# design.net
KiCad netlist of a schematic drawn in Altium Designer
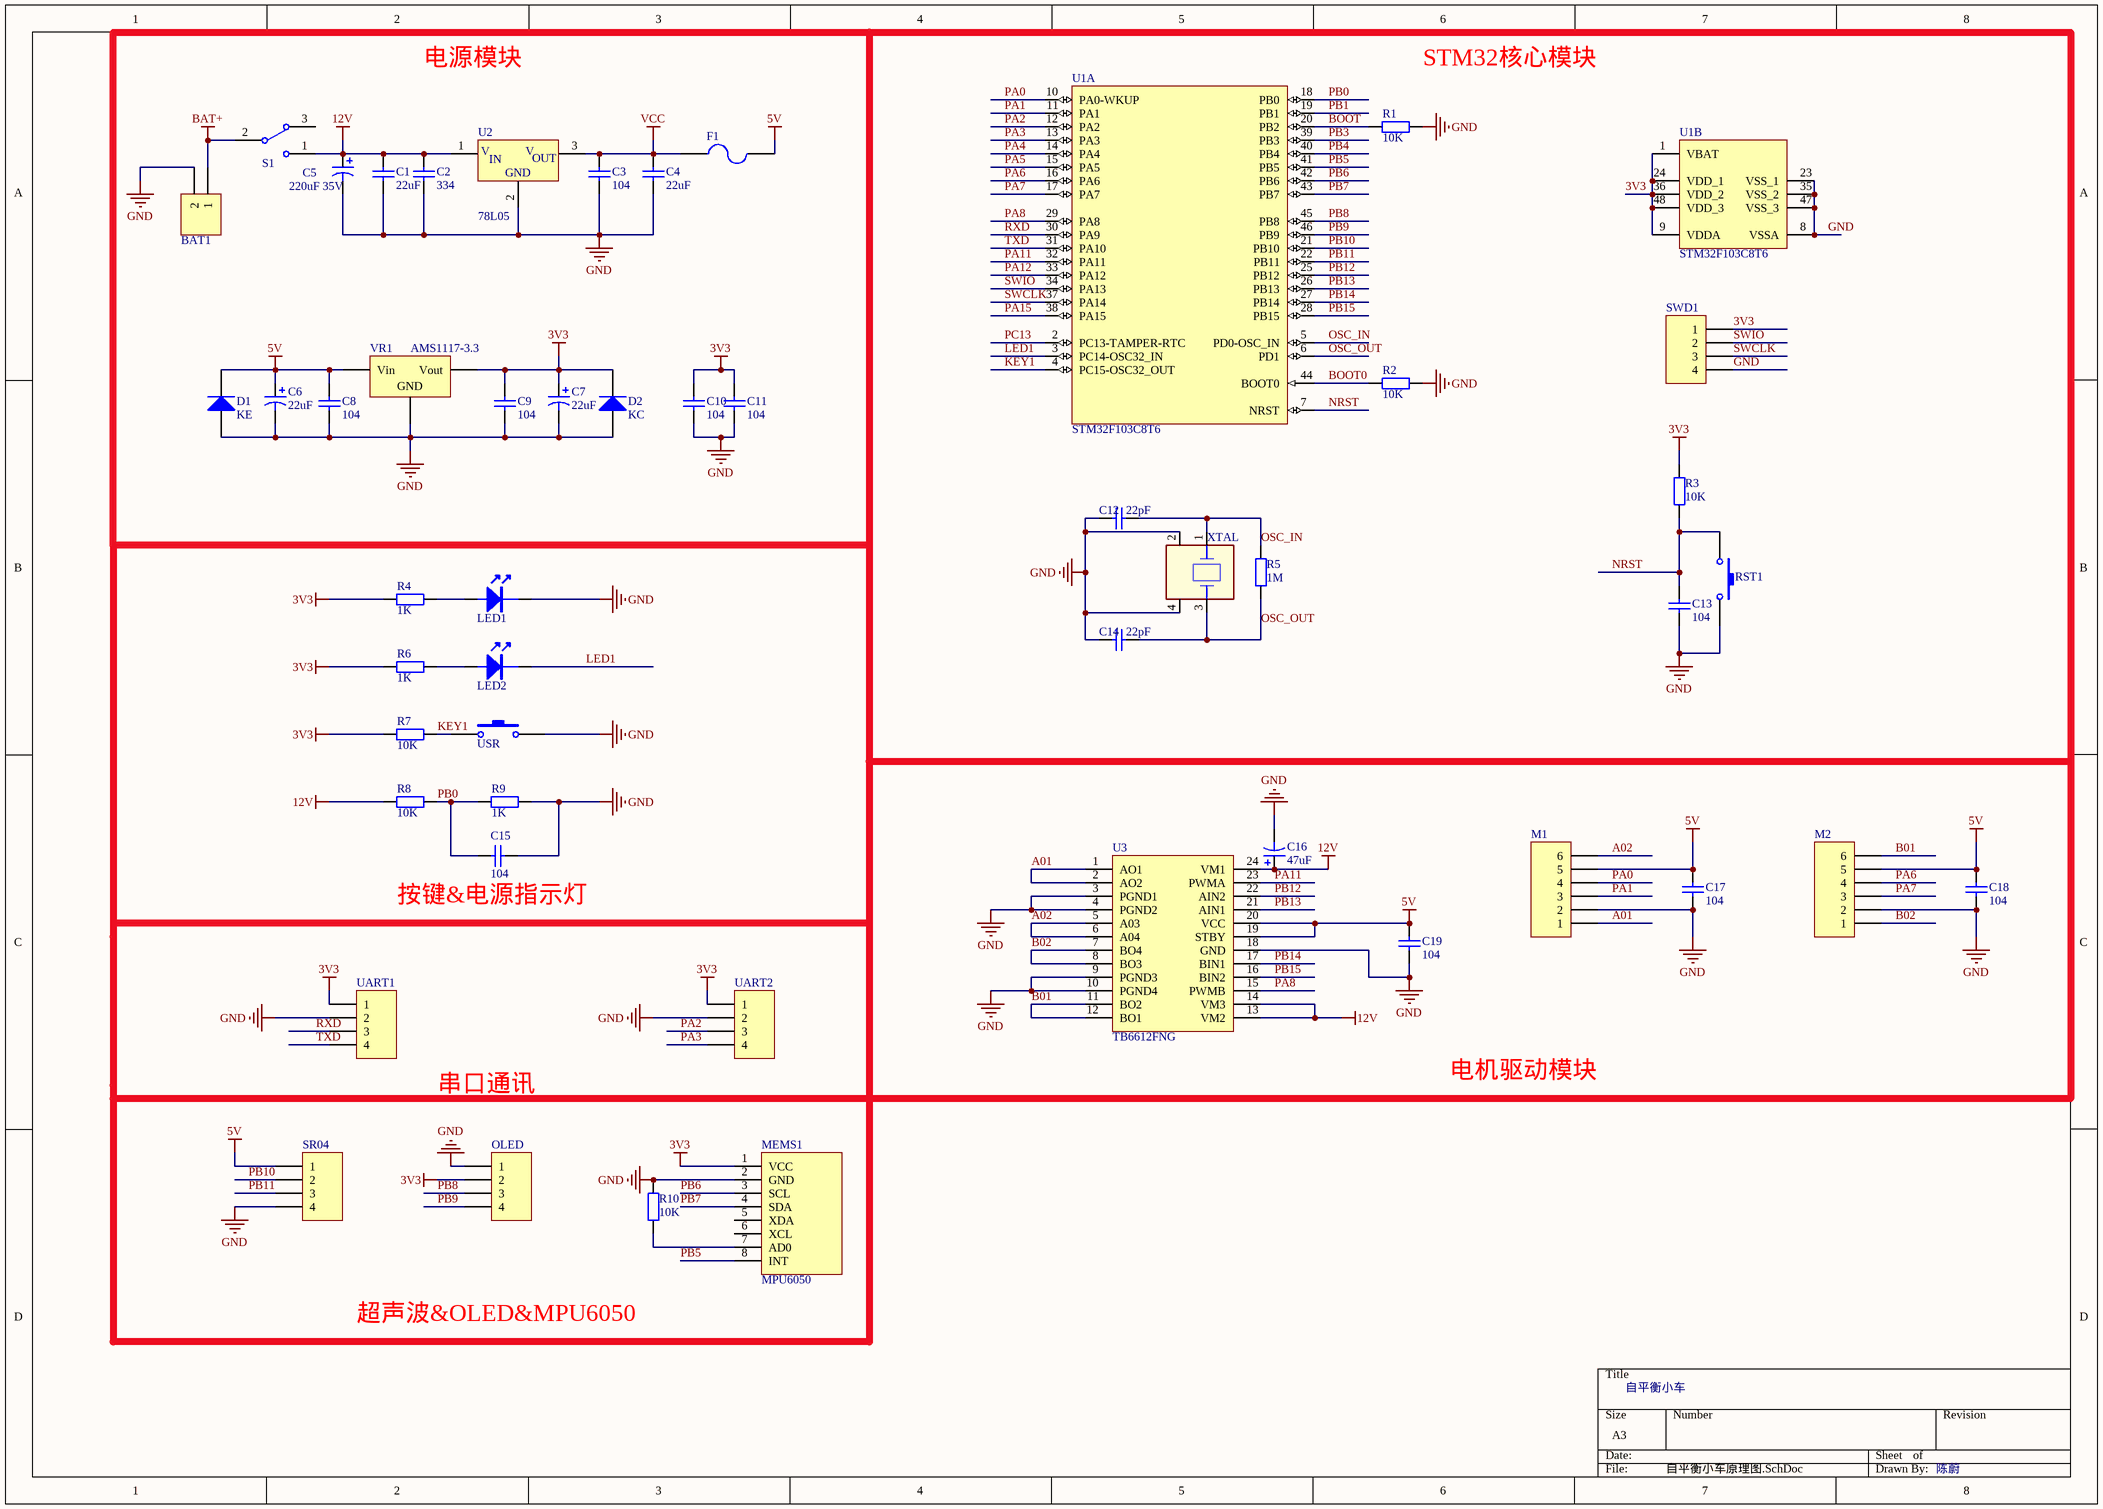
[diagram p0: 自平衡小车原理图.SchDoc]

(export (version "E")
  (design (tool "Eeschema 10.0.6"))
  (components
    (comp (ref "BAT1")
      (value "Header 2")
      (footprint "XT30-PW-M")
      (description "Header, 2-Pin")
      (fields (field (name "PUBLISHER") "Altium Limited"))
      (libsource (lib "F1C6Balance_a0") (part "Header 2"))
    )
    (comp (ref "C1")
      (value "22uF")
      (footprint "0603_C_f")
      (description "贴片电容")
      (libsource (lib "F1C6Balance_a0") (part "0805 22uF (226) 20% 25V"))
    )
    (comp (ref "C2")
      (value "334")
      (footprint "0603_C_f")
      (description "贴片电容")
      (libsource (lib "F1C6Balance_a0") (part "0603 100nF (104) 10% 50V_1"))
    )
    (comp (ref "C3")
      (value "104")
      (footprint "0603_C_f")
      (description "贴片电容")
      (libsource (lib "F1C6Balance_a0") (part "0603 100nF (104) 10% 50V"))
    )
    (comp (ref "C4")
      (value "22uF")
      (footprint "0603_C_f")
      (description "贴片电容")
      (libsource (lib "F1C6Balance_a0") (part "0805 22uF (226) 20% 25V"))
    )
    (comp (ref "C5")
      (value "220uF 35V")
      (footprint "CM E(8*10.2)")
      (description "Polarized Capacitor (Radial)")
      (fields (field (name "PUBLISHER") "Altium Limited"))
      (libsource (lib "F1C6Balance_a0") (part "Cap Pol1_1"))
    )
    (comp (ref "C6")
      (value "22uF")
      (footprint "CD A(3216)")
      (description "Polarized Capacitor (Radial)")
      (fields (field (name "Comment") "T22uF") (field (name "PUBLISHER") "Altium Limited"))
      (libsource (lib "F1C6Balance_a0") (part "Cap Pol1_2"))
    )
    (comp (ref "C7")
      (value "22uF")
      (footprint "CD A(3216)")
      (description "Polarized Capacitor (Radial)")
      (fields (field (name "Comment") "T22uF") (field (name "PUBLISHER") "Altium Limited"))
      (libsource (lib "F1C6Balance_a0") (part "Cap Pol1_2"))
    )
    (comp (ref "C8")
      (value "104")
      (footprint "0603_C_f")
      (description "贴片电容")
      (libsource (lib "F1C6Balance_a0") (part "0603 100nF (104) 10% 50V"))
    )
    (comp (ref "C9")
      (value "104")
      (footprint "0603_C_f")
      (description "贴片电容")
      (libsource (lib "F1C6Balance_a0") (part "0603 100nF (104) 10% 50V"))
    )
    (comp (ref "C10")
      (value "104")
      (footprint "0603_C_f")
      (description "贴片电容")
      (libsource (lib "F1C6Balance_a0") (part "0603 100nF (104) 10% 50V"))
    )
    (comp (ref "C11")
      (value "104")
      (footprint "0603_C_f")
      (description "贴片电容")
      (libsource (lib "F1C6Balance_a0") (part "0603 100nF (104) 10% 50V"))
    )
    (comp (ref "C12")
      (value "22pF")
      (footprint "0603_C_f")
      (description "贴片电容")
      (libsource (lib "F1C6Balance_a0") (part "0603 22pF (220) 5% 50V"))
    )
    (comp (ref "C13")
      (value "104")
      (footprint "0603_C_f")
      (description "贴片电容")
      (libsource (lib "F1C6Balance_a0") (part "0603 100nF (104) 10% 50V"))
    )
    (comp (ref "C14")
      (value "22pF")
      (footprint "0603_C_f")
      (description "贴片电容")
      (libsource (lib "F1C6Balance_a0") (part "0603 22pF (220) 5% 50V"))
    )
    (comp (ref "C15")
      (value "104")
      (footprint "0603_C_f")
      (description "贴片电容")
      (libsource (lib "F1C6Balance_a0") (part "0603 100nF (104) 10% 50V"))
    )
    (comp (ref "C16")
      (value "47uF")
      (footprint "CM D(6.3*7.7)")
      (description "Polarized Capacitor (Radial)")
      (fields (field (name "PUBLISHER") "Altium Limited"))
      (libsource (lib "F1C6Balance_a0") (part "Cap Pol1"))
    )
    (comp (ref "C17")
      (value "104")
      (footprint "0603_C_f")
      (description "贴片电容")
      (libsource (lib "F1C6Balance_a0") (part "0603 100nF (104) 10% 50V"))
    )
    (comp (ref "C18")
      (value "104")
      (footprint "0603_C_f")
      (description "贴片电容")
      (libsource (lib "F1C6Balance_a0") (part "0603 100nF (104) 10% 50V"))
    )
    (comp (ref "C19")
      (value "104")
      (footprint "0603_C_f")
      (description "贴片电容")
      (libsource (lib "F1C6Balance_a0") (part "0603 100nF (104) 10% 50V"))
    )
    (comp (ref "D1")
      (value "KE")
      (footprint "SMB")
      (description "Default Diode")
      (fields (field (name "PUBLISHER") "Altium Limited"))
      (libsource (lib "F1C6Balance_a0") (part "Diode_1"))
    )
    (comp (ref "D2")
      (value "KC")
      (footprint "SMB")
      (description "Default Diode")
      (fields (field (name "PUBLISHER") "Altium Limited"))
      (libsource (lib "F1C6Balance_a0") (part "Diode_2"))
    )
    (comp (ref "F1")
      (value "F1")
      (footprint "0805_R")
      (description "Fuse")
      (fields (field (name "PUBLISHER") "Altium Limited"))
      (libsource (lib "F1C6Balance_a0") (part "Fuse 2"))
    )
    (comp (ref "LED1")
      (value "LED")
      (footprint "LED-0603_GREEN")
      (libsource (lib "F1C6Balance_a0") (part "LED"))
    )
    (comp (ref "LED2")
      (value "LED")
      (footprint "LED-0603_GREEN")
      (libsource (lib "F1C6Balance_a0") (part "LED"))
    )
    (comp (ref "M1")
      (value "Header 6")
      (footprint "XH2.54-WI-6P")
      (description "Header, 6-Pin")
      (fields (field (name "PUBLISHER") "Altium Limited"))
      (libsource (lib "F1C6Balance_a0") (part "Header 6"))
    )
    (comp (ref "M2")
      (value "Header 6")
      (footprint "XH2.54-WI-6P")
      (description "Header, 6-Pin")
      (fields (field (name "PUBLISHER") "Altium Limited"))
      (libsource (lib "F1C6Balance_a0") (part "Header 6"))
    )
    (comp (ref "MEMS1")
      (value "MPU6050")
      (footprint "MPU6050")
      (libsource (lib "F1C6Balance_a0") (part "GY-521"))
    )
    (comp (ref "OLED")
      (value "Header 4")
      (footprint "HDR1X4")
      (description "Header, 4-Pin")
      (fields (field (name "PUBLISHER") "Altium Limited"))
      (libsource (lib "F1C6Balance_a0") (part "Header 4_1"))
    )
    (comp (ref "R1")
      (value "10K")
      (footprint "0603_R_F")
      (description "贴片电阻")
      (libsource (lib "F1C6Balance_a0") (part "0603 10KΩ (1002) 1%"))
    )
    (comp (ref "R2")
      (value "10K")
      (footprint "0603_R_F")
      (description "贴片电阻")
      (libsource (lib "F1C6Balance_a0") (part "0603 10KΩ (1002) 1%"))
    )
    (comp (ref "R3")
      (value "10K")
      (footprint "0603_R_F")
      (description "贴片电阻")
      (libsource (lib "") (part "0603 10KΩ (1002) 1%_1"))
    )
    (comp (ref "R4")
      (value "1K")
      (footprint "0603_R_F")
      (description "贴片电阻")
      (libsource (lib "F1C6Balance_a0") (part "0603 1KΩ (1001) 1%"))
    )
    (comp (ref "R5")
      (value "1M")
      (footprint "0603_R_F")
      (description "贴片电阻")
      (libsource (lib "F1C6Balance_a0") (part "0603 1MΩ (1004) 1%"))
    )
    (comp (ref "R6")
      (value "1K")
      (footprint "0603_R_F")
      (description "贴片电阻")
      (libsource (lib "F1C6Balance_a0") (part "0603 1KΩ (1001) 1%"))
    )
    (comp (ref "R7")
      (value "10K")
      (footprint "0603_R_F")
      (description "贴片电阻")
      (libsource (lib "F1C6Balance_a0") (part "0603 10KΩ (1002) 1%"))
    )
    (comp (ref "R8")
      (value "10K")
      (footprint "0603_R_F")
      (description "贴片电阻")
      (libsource (lib "F1C6Balance_a0") (part "0603 10KΩ (1002) 1%"))
    )
    (comp (ref "R9")
      (value "1K")
      (footprint "0603_R_F")
      (description "贴片电阻")
      (libsource (lib "F1C6Balance_a0") (part "0603 1KΩ (1001) 1%"))
    )
    (comp (ref "R10")
      (value "10K")
      (footprint "0603_R_F")
      (description "贴片电阻")
      (libsource (lib "") (part "0603 10KΩ (1002) 1%_1"))
    )
    (comp (ref "RST1")
      (value "SW-PB")
      (footprint "KEY")
      (description "Switch")
      (fields (field (name "PUBLISHER") "Altium Limited"))
      (libsource (lib "F1C6Balance_a0") (part "SW-PB"))
    )
    (comp (ref "S1")
      (value "SW-SPDT")
      (footprint "SW-TH_SK-12D02-VG5")
      (description "SPDT Subminiature Toggle Switch, Right Angle Mounting, Vertical Actuation")
      (fields (field (name "PUBLISHER") "Altium Limited"))
      (libsource (lib "F1C6Balance_a0") (part "SW-SPDT"))
    )
    (comp (ref "SR04")
      (value "Header 4")
      (footprint "HDR1X4")
      (description "Header, 4-Pin")
      (fields (field (name "PUBLISHER") "Altium Limited"))
      (libsource (lib "F1C6Balance_a0") (part "Header 4_1"))
    )
    (comp (ref "SWD1")
      (value "Header 4")
      (footprint "HDR1X4")
      (description "Header, 4-Pin")
      (fields (field (name "PUBLISHER") "Altium Limited"))
      (libsource (lib "F1C6Balance_a0") (part "Header 4"))
    )
    (comp (ref "U1")
      (value "STM32F103C8T6")
      (footprint "LQFP48 7X7_N")
      (description "ARM")
      (libsource (lib "F1C6Balance_a0") (part "STM32F103C8T6"))
    )
    (comp (ref "U2")
      (value "78L05")
      (footprint "TO252")
      (description "3-Terminal Positive Voltage Regulator")
      (libsource (lib "F1C6Balance_a0") (part "78L05"))
    )
    (comp (ref "U3")
      (value "TB6612FNG")
      (footprint "SSOP-24_208mil")
      (libsource (lib "F1C6Balance_a0") (part "TB6612FNG"))
    )
    (comp (ref "UART1")
      (value "Header 4")
      (footprint "HDR1X4")
      (description "Header, 4-Pin")
      (fields (field (name "PUBLISHER") "Altium Limited"))
      (libsource (lib "F1C6Balance_a0") (part "Header 4_1"))
    )
    (comp (ref "UART2")
      (value "Header 4")
      (footprint "HDR1X4")
      (description "Header, 4-Pin")
      (fields (field (name "PUBLISHER") "Altium Limited"))
      (libsource (lib "F1C6Balance_a0") (part "Header 4_1"))
    )
    (comp (ref "USR")
      (value "SW-PB")
      (footprint "KEY")
      (description "Switch")
      (fields (field (name "PUBLISHER") "Altium Limited"))
      (libsource (lib "F1C6Balance_a0") (part "SW-PB"))
    )
    (comp (ref "VR1")
      (value "AMS1117-3.3")
      (footprint "SOT223_N")
      (description "低压差线性稳压(LDO)")
      (libsource (lib "F1C6Balance_a0") (part "SOT-223 AMS1117-3.3"))
    )
    (comp (ref "XTAL")
      (value "XTAL-4P")
      (footprint "OSC 3225-4P")
      (libsource (lib "F1C6Balance_a0") (part "XTAL-4P"))
    )
  )
  (nets
    (net (code "1") (name "/A01") (class "Default")
      (node (ref "M1") (pin "1") (pinfunction "1_1") (pintype "passive"))
      (node (ref "U3") (pin "1") (pinfunction "AO1_1") (pintype "passive"))
      (node (ref "U3") (pin "2") (pinfunction "AO2_2") (pintype "passive"))
    )
    (net (code "2") (name "/A02") (class "Default")
      (node (ref "M1") (pin "6") (pinfunction "6_6") (pintype "passive"))
      (node (ref "U3") (pin "5") (pinfunction "A03_5") (pintype "passive"))
      (node (ref "U3") (pin "6") (pinfunction "A04_6") (pintype "passive"))
    )
    (net (code "3") (name "/B01") (class "Default")
      (node (ref "M2") (pin "6") (pinfunction "6_6") (pintype "passive"))
      (node (ref "U3") (pin "11") (pinfunction "BO2_11") (pintype "passive"))
      (node (ref "U3") (pin "12") (pinfunction "BO1_12") (pintype "passive"))
    )
    (net (code "4") (name "/B02") (class "Default")
      (node (ref "M2") (pin "1") (pinfunction "1_1") (pintype "passive"))
      (node (ref "U3") (pin "7") (pinfunction "BO4_7") (pintype "passive"))
      (node (ref "U3") (pin "8") (pinfunction "BO3_8") (pintype "passive"))
    )
    (net (code "5") (name "/BOOT") (class "Default")
      (node (ref "R1") (pin "1") (pinfunction "1_1") (pintype "passive"))
      (node (ref "U1") (pin "20") (pinfunction "PB2_20") (pintype "bidirectional"))
    )
    (net (code "6") (name "/BOOT0") (class "Default")
      (node (ref "R2") (pin "1") (pinfunction "1_1") (pintype "passive"))
      (node (ref "U1") (pin "44") (pinfunction "BOOT0_44") (pintype "input"))
    )
    (net (code "7") (name "/KEY1") (class "Default")
      (node (ref "R7") (pin "2") (pinfunction "2_2") (pintype "passive"))
      (node (ref "U1") (pin "4") (pinfunction "PC15-OSC32_OUT_4") (pintype "bidirectional"))
      (node (ref "USR") (pin "1") (pinfunction "1_1") (pintype "passive"))
    )
    (net (code "8") (name "/LED1") (class "Default")
      (node (ref "LED2") (pin "2") (pinfunction "2_2") (pintype "passive"))
      (node (ref "U1") (pin "3") (pinfunction "PC14-OSC32_IN_3") (pintype "bidirectional"))
    )
    (net (code "9") (name "/NRST") (class "Default")
      (node (ref "C13") (pin "2") (pinfunction "2_2") (pintype "passive"))
      (node (ref "R3") (pin "1") (pinfunction "1_1") (pintype "passive"))
      (node (ref "RST1") (pin "1") (pinfunction "1_1") (pintype "passive"))
      (node (ref "U1") (pin "7") (pinfunction "NRST_7") (pintype "bidirectional"))
    )
    (net (code "10") (name "/OSC_IN") (class "Default")
      (node (ref "C12") (pin "2") (pinfunction "2_2") (pintype "passive"))
      (node (ref "R5") (pin "2") (pinfunction "2_2") (pintype "passive"))
      (node (ref "U1") (pin "5") (pinfunction "PD0-OSC_IN_5") (pintype "bidirectional"))
      (node (ref "XTAL") (pin "1") (pinfunction "1_1") (pintype "passive"))
    )
    (net (code "11") (name "/OSC_OUT") (class "Default")
      (node (ref "C14") (pin "2") (pinfunction "2_2") (pintype "passive"))
      (node (ref "R5") (pin "1") (pinfunction "1_1") (pintype "passive"))
      (node (ref "U1") (pin "6") (pinfunction "PD1_6") (pintype "bidirectional"))
      (node (ref "XTAL") (pin "3") (pinfunction "3_3") (pintype "passive"))
    )
    (net (code "12") (name "/PA0") (class "Default")
      (node (ref "M1") (pin "4") (pinfunction "4_4") (pintype "passive"))
      (node (ref "U1") (pin "10") (pinfunction "PA0-WKUP_10") (pintype "bidirectional"))
    )
    (net (code "13") (name "/PA1") (class "Default")
      (node (ref "M1") (pin "3") (pinfunction "3_3") (pintype "passive"))
      (node (ref "U1") (pin "11") (pinfunction "PA1_11") (pintype "bidirectional"))
    )
    (net (code "14") (name "/PA2") (class "Default")
      (node (ref "U1") (pin "12") (pinfunction "PA2_12") (pintype "bidirectional"))
      (node (ref "UART2") (pin "3") (pinfunction "3_3") (pintype "passive"))
    )
    (net (code "15") (name "/PA3") (class "Default")
      (node (ref "U1") (pin "13") (pinfunction "PA3_13") (pintype "bidirectional"))
      (node (ref "UART2") (pin "4") (pinfunction "4_4") (pintype "passive"))
    )
    (net (code "16") (name "/PA4") (class "Default")
      (node (ref "U1") (pin "14") (pinfunction "PA4_14") (pintype "bidirectional"))
    )
    (net (code "17") (name "/PA5") (class "Default")
      (node (ref "U1") (pin "15") (pinfunction "PA5_15") (pintype "bidirectional"))
    )
    (net (code "18") (name "/PA6") (class "Default")
      (node (ref "M2") (pin "4") (pinfunction "4_4") (pintype "passive"))
      (node (ref "U1") (pin "16") (pinfunction "PA6_16") (pintype "bidirectional"))
    )
    (net (code "19") (name "/PA7") (class "Default")
      (node (ref "M2") (pin "3") (pinfunction "3_3") (pintype "passive"))
      (node (ref "U1") (pin "17") (pinfunction "PA7_17") (pintype "bidirectional"))
    )
    (net (code "20") (name "/PA8") (class "Default")
      (node (ref "U1") (pin "29") (pinfunction "PA8_29") (pintype "bidirectional"))
      (node (ref "U3") (pin "15") (pinfunction "PWMB_15") (pintype "passive"))
    )
    (net (code "21") (name "/PA11") (class "Default")
      (node (ref "U1") (pin "32") (pinfunction "PA11_32") (pintype "bidirectional"))
      (node (ref "U3") (pin "23") (pinfunction "PWMA_23") (pintype "passive"))
    )
    (net (code "22") (name "/PA12") (class "Default")
      (node (ref "U1") (pin "33") (pinfunction "PA12_33") (pintype "bidirectional"))
    )
    (net (code "23") (name "/PA15") (class "Default")
      (node (ref "U1") (pin "38") (pinfunction "PA15_38") (pintype "bidirectional"))
    )
    (net (code "24") (name "/PB0") (class "Default")
      (node (ref "C15") (pin "1") (pinfunction "1_1") (pintype "passive"))
      (node (ref "R8") (pin "2") (pinfunction "2_2") (pintype "passive"))
      (node (ref "R9") (pin "1") (pinfunction "1_1") (pintype "passive"))
      (node (ref "U1") (pin "18") (pinfunction "PB0_18") (pintype "bidirectional"))
    )
    (net (code "25") (name "/PB1") (class "Default")
      (node (ref "U1") (pin "19") (pinfunction "PB1_19") (pintype "bidirectional"))
    )
    (net (code "26") (name "/PB3") (class "Default")
      (node (ref "U1") (pin "39") (pinfunction "PB3_39") (pintype "bidirectional"))
    )
    (net (code "27") (name "/PB4") (class "Default")
      (node (ref "U1") (pin "40") (pinfunction "PB4_40") (pintype "bidirectional"))
    )
    (net (code "28") (name "/PB5") (class "Default")
      (node (ref "MEMS1") (pin "8") (pinfunction "INT_8") (pintype "passive"))
      (node (ref "U1") (pin "41") (pinfunction "PB5_41") (pintype "bidirectional"))
    )
    (net (code "29") (name "/PB6") (class "Default")
      (node (ref "MEMS1") (pin "3") (pinfunction "SCL_3") (pintype "passive"))
      (node (ref "U1") (pin "42") (pinfunction "PB6_42") (pintype "bidirectional"))
    )
    (net (code "30") (name "/PB7") (class "Default")
      (node (ref "MEMS1") (pin "4") (pinfunction "SDA_4") (pintype "passive"))
      (node (ref "U1") (pin "43") (pinfunction "PB7_43") (pintype "bidirectional"))
    )
    (net (code "31") (name "/PB8") (class "Default")
      (node (ref "OLED") (pin "3") (pinfunction "3_3") (pintype "passive"))
      (node (ref "U1") (pin "45") (pinfunction "PB8_45") (pintype "bidirectional"))
    )
    (net (code "32") (name "/PB9") (class "Default")
      (node (ref "OLED") (pin "4") (pinfunction "4_4") (pintype "passive"))
      (node (ref "U1") (pin "46") (pinfunction "PB9_46") (pintype "bidirectional"))
    )
    (net (code "33") (name "/PB10") (class "Default")
      (node (ref "SR04") (pin "2") (pinfunction "2_2") (pintype "passive"))
      (node (ref "U1") (pin "21") (pinfunction "PB10_21") (pintype "bidirectional"))
    )
    (net (code "34") (name "/PB11") (class "Default")
      (node (ref "SR04") (pin "3") (pinfunction "3_3") (pintype "passive"))
      (node (ref "U1") (pin "22") (pinfunction "PB11_22") (pintype "bidirectional"))
    )
    (net (code "35") (name "/PB12") (class "Default")
      (node (ref "U1") (pin "25") (pinfunction "PB12_25") (pintype "bidirectional"))
      (node (ref "U3") (pin "22") (pinfunction "AIN2_22") (pintype "passive"))
    )
    (net (code "36") (name "/PB13") (class "Default")
      (node (ref "U1") (pin "26") (pinfunction "PB13_26") (pintype "bidirectional"))
      (node (ref "U3") (pin "21") (pinfunction "AIN1_21") (pintype "passive"))
    )
    (net (code "37") (name "/PB14") (class "Default")
      (node (ref "U1") (pin "27") (pinfunction "PB14_27") (pintype "bidirectional"))
      (node (ref "U3") (pin "17") (pinfunction "BIN1_17") (pintype "passive"))
    )
    (net (code "38") (name "/PB15") (class "Default")
      (node (ref "U1") (pin "28") (pinfunction "PB15_28") (pintype "bidirectional"))
      (node (ref "U3") (pin "16") (pinfunction "BIN2_16") (pintype "passive"))
    )
    (net (code "39") (name "/PC13") (class "Default")
      (node (ref "U1") (pin "2") (pinfunction "PC13-TAMPER-RTC_2") (pintype "bidirectional"))
    )
    (net (code "40") (name "/RXD") (class "Default")
      (node (ref "U1") (pin "30") (pinfunction "PA9_30") (pintype "bidirectional"))
      (node (ref "UART1") (pin "3") (pinfunction "3_3") (pintype "passive"))
    )
    (net (code "41") (name "/SWCLK") (class "Default")
      (node (ref "SWD1") (pin "3") (pinfunction "3_3") (pintype "passive"))
      (node (ref "U1") (pin "37") (pinfunction "PA14_37") (pintype "bidirectional"))
    )
    (net (code "42") (name "/SWIO") (class "Default")
      (node (ref "SWD1") (pin "2") (pinfunction "2_2") (pintype "passive"))
      (node (ref "U1") (pin "34") (pinfunction "PA13_34") (pintype "bidirectional"))
    )
    (net (code "43") (name "/TXD") (class "Default")
      (node (ref "U1") (pin "31") (pinfunction "PA10_31") (pintype "bidirectional"))
      (node (ref "UART1") (pin "4") (pinfunction "4_4") (pintype "passive"))
    )
    (net (code "44") (name "3V3") (class "Default")
      (node (ref "C10") (pin "2") (pinfunction "2_2") (pintype "passive"))
      (node (ref "C11") (pin "2") (pinfunction "2_2") (pintype "passive"))
      (node (ref "C7") (pin "1") (pinfunction "1_1") (pintype "passive"))
      (node (ref "C9") (pin "2") (pinfunction "2_2") (pintype "passive"))
      (node (ref "D2") (pin "2") (pinfunction "K_2") (pintype "passive"))
      (node (ref "MEMS1") (pin "1") (pinfunction "VCC_1") (pintype "passive"))
      (node (ref "OLED") (pin "2") (pinfunction "2_2") (pintype "passive"))
      (node (ref "R3") (pin "2") (pinfunction "2_2") (pintype "passive"))
      (node (ref "R4") (pin "1") (pinfunction "1_1") (pintype "passive"))
      (node (ref "R6") (pin "1") (pinfunction "1_1") (pintype "passive"))
      (node (ref "R7") (pin "1") (pinfunction "1_1") (pintype "passive"))
      (node (ref "SWD1") (pin "1") (pinfunction "1_1") (pintype "passive"))
      (node (ref "U1") (pin "1") (pinfunction "VBAT_1") (pintype "power_in"))
      (node (ref "U1") (pin "24") (pinfunction "VDD_1_24") (pintype "power_in"))
      (node (ref "U1") (pin "36") (pinfunction "VDD_2_36") (pintype "power_in"))
      (node (ref "U1") (pin "48") (pinfunction "VDD_3_48") (pintype "power_in"))
      (node (ref "U1") (pin "9") (pinfunction "VDDA_9") (pintype "power_in"))
      (node (ref "UART1") (pin "1") (pinfunction "1_1") (pintype "passive"))
      (node (ref "UART2") (pin "1") (pinfunction "1_1") (pintype "passive"))
      (node (ref "VR1") (pin "2") (pinfunction "Vout_2") (pintype "passive"))
    )
    (net (code "45") (name "5V") (class "Default")
      (node (ref "C17") (pin "2") (pinfunction "2_2") (pintype "passive"))
      (node (ref "C18") (pin "2") (pinfunction "2_2") (pintype "passive"))
      (node (ref "C19") (pin "2") (pinfunction "2_2") (pintype "passive"))
      (node (ref "C6") (pin "1") (pinfunction "1_1") (pintype "passive"))
      (node (ref "C8") (pin "2") (pinfunction "2_2") (pintype "passive"))
      (node (ref "D1") (pin "2") (pinfunction "K_2") (pintype "passive"))
      (node (ref "F1") (pin "2") (pinfunction "2_2") (pintype "passive"))
      (node (ref "M1") (pin "5") (pinfunction "5_5") (pintype "passive"))
      (node (ref "M2") (pin "5") (pinfunction "5_5") (pintype "passive"))
      (node (ref "SR04") (pin "1") (pinfunction "1_1") (pintype "passive"))
      (node (ref "U3") (pin "19") (pinfunction "STBY_19") (pintype "passive"))
      (node (ref "U3") (pin "20") (pinfunction "VCC_20") (pintype "passive"))
      (node (ref "VR1") (pin "3") (pinfunction "Vin_3") (pintype "passive"))
    )
    (net (code "46") (name "12V") (class "Default")
      (node (ref "C1") (pin "2") (pinfunction "2_2") (pintype "passive"))
      (node (ref "C16") (pin "1") (pinfunction "1_1") (pintype "passive"))
      (node (ref "C2") (pin "2") (pinfunction "2_2") (pintype "passive"))
      (node (ref "C5") (pin "1") (pinfunction "1_1") (pintype "passive"))
      (node (ref "R8") (pin "1") (pinfunction "1_1") (pintype "passive"))
      (node (ref "S1") (pin "1") (pinfunction "1_1") (pintype "passive"))
      (node (ref "U2") (pin "1") (pinfunction "VIN_1") (pintype "passive"))
      (node (ref "U3") (pin "13") (pinfunction "VM2_13") (pintype "passive"))
      (node (ref "U3") (pin "14") (pinfunction "VM3_14") (pintype "passive"))
      (node (ref "U3") (pin "24") (pinfunction "VM1_24") (pintype "passive"))
    )
    (net (code "47") (name "BAT+") (class "Default")
      (node (ref "BAT1") (pin "1") (pinfunction "1_1") (pintype "passive"))
      (node (ref "S1") (pin "2") (pinfunction "2_2") (pintype "passive"))
    )
    (net (code "48") (name "GND") (class "Default")
      (node (ref "BAT1") (pin "2") (pinfunction "2_2") (pintype "passive"))
      (node (ref "C1") (pin "1") (pinfunction "1_1") (pintype "passive"))
      (node (ref "C10") (pin "1") (pinfunction "1_1") (pintype "passive"))
      (node (ref "C11") (pin "1") (pinfunction "1_1") (pintype "passive"))
      (node (ref "C12") (pin "1") (pinfunction "1_1") (pintype "passive"))
      (node (ref "C13") (pin "1") (pinfunction "1_1") (pintype "passive"))
      (node (ref "C14") (pin "1") (pinfunction "1_1") (pintype "passive"))
      (node (ref "C15") (pin "2") (pinfunction "2_2") (pintype "passive"))
      (node (ref "C16") (pin "2") (pinfunction "2_2") (pintype "passive"))
      (node (ref "C17") (pin "1") (pinfunction "1_1") (pintype "passive"))
      (node (ref "C18") (pin "1") (pinfunction "1_1") (pintype "passive"))
      (node (ref "C19") (pin "1") (pinfunction "1_1") (pintype "passive"))
      (node (ref "C2") (pin "1") (pinfunction "1_1") (pintype "passive"))
      (node (ref "C3") (pin "1") (pinfunction "1_1") (pintype "passive"))
      (node (ref "C4") (pin "1") (pinfunction "1_1") (pintype "passive"))
      (node (ref "C5") (pin "2") (pinfunction "2_2") (pintype "passive"))
      (node (ref "C6") (pin "2") (pinfunction "2_2") (pintype "passive"))
      (node (ref "C7") (pin "2") (pinfunction "2_2") (pintype "passive"))
      (node (ref "C8") (pin "1") (pinfunction "1_1") (pintype "passive"))
      (node (ref "C9") (pin "1") (pinfunction "1_1") (pintype "passive"))
      (node (ref "D1") (pin "1") (pinfunction "A_1") (pintype "passive"))
      (node (ref "D2") (pin "1") (pinfunction "A_1") (pintype "passive"))
      (node (ref "LED1") (pin "2") (pinfunction "2_2") (pintype "passive"))
      (node (ref "M1") (pin "2") (pinfunction "2_2") (pintype "passive"))
      (node (ref "M2") (pin "2") (pinfunction "2_2") (pintype "passive"))
      (node (ref "MEMS1") (pin "2") (pinfunction "GND_2") (pintype "passive"))
      (node (ref "OLED") (pin "1") (pinfunction "1_1") (pintype "passive"))
      (node (ref "R1") (pin "2") (pinfunction "2_2") (pintype "passive"))
      (node (ref "R10") (pin "2") (pinfunction "2_2") (pintype "passive"))
      (node (ref "R2") (pin "2") (pinfunction "2_2") (pintype "passive"))
      (node (ref "R9") (pin "2") (pinfunction "2_2") (pintype "passive"))
      (node (ref "RST1") (pin "2") (pinfunction "2_2") (pintype "passive"))
      (node (ref "SR04") (pin "4") (pinfunction "4_4") (pintype "passive"))
      (node (ref "SWD1") (pin "4") (pinfunction "4_4") (pintype "passive"))
      (node (ref "U1") (pin "23") (pinfunction "VSS_1_23") (pintype "power_in"))
      (node (ref "U1") (pin "35") (pinfunction "VSS_2_35") (pintype "power_in"))
      (node (ref "U1") (pin "47") (pinfunction "VSS_3_47") (pintype "power_in"))
      (node (ref "U1") (pin "8") (pinfunction "VSSA_8") (pintype "power_in"))
      (node (ref "U2") (pin "2") (pinfunction "GND_2") (pintype "passive"))
      (node (ref "U3") (pin "10") (pinfunction "PGND4_10") (pintype "passive"))
      (node (ref "U3") (pin "18") (pinfunction "GND_18") (pintype "passive"))
      (node (ref "U3") (pin "3") (pinfunction "PGND1_3") (pintype "passive"))
      (node (ref "U3") (pin "4") (pinfunction "PGND2_4") (pintype "passive"))
      (node (ref "U3") (pin "9") (pinfunction "PGND3_9") (pintype "passive"))
      (node (ref "UART1") (pin "2") (pinfunction "2_2") (pintype "passive"))
      (node (ref "UART2") (pin "2") (pinfunction "2_2") (pintype "passive"))
      (node (ref "USR") (pin "2") (pinfunction "2_2") (pintype "passive"))
      (node (ref "VR1") (pin "1") (pinfunction "GND_1") (pintype "passive"))
      (node (ref "XTAL") (pin "2") (pinfunction "2_2") (pintype "passive"))
      (node (ref "XTAL") (pin "4") (pinfunction "4_4") (pintype "passive"))
    )
    (net (code "49") (name "Net-(LED1-Pad1)") (class "Default")
      (node (ref "LED1") (pin "1") (pinfunction "1_1") (pintype "passive"))
      (node (ref "R4") (pin "2") (pinfunction "2_2") (pintype "passive"))
    )
    (net (code "50") (name "Net-(LED2-Pad1)") (class "Default")
      (node (ref "LED2") (pin "1") (pinfunction "1_1") (pintype "passive"))
      (node (ref "R6") (pin "2") (pinfunction "2_2") (pintype "passive"))
    )
    (net (code "51") (name "Net-(MEMS1-AD0)") (class "Default")
      (node (ref "MEMS1") (pin "7") (pinfunction "AD0_7") (pintype "passive"))
      (node (ref "R10") (pin "1") (pinfunction "1_1") (pintype "passive"))
    )
    (net (code "52") (name "VCC") (class "Default")
      (node (ref "C3") (pin "2") (pinfunction "2_2") (pintype "passive"))
      (node (ref "C4") (pin "2") (pinfunction "2_2") (pintype "passive"))
      (node (ref "F1") (pin "1") (pinfunction "1_1") (pintype "passive"))
      (node (ref "U2") (pin "3") (pinfunction "VOUT_3") (pintype "passive"))
    )
    (net (code "53") (name "unconnected-(MEMS1-XCL-Pad6)") (class "Default")
      (node (ref "MEMS1") (pin "6") (pinfunction "XCL_6") (pintype "passive"))
    )
    (net (code "54") (name "unconnected-(MEMS1-XDA-Pad5)") (class "Default")
      (node (ref "MEMS1") (pin "5") (pinfunction "XDA_5") (pintype "passive"))
    )
    (net (code "55") (name "unconnected-(S1-Pad3)") (class "Default")
      (node (ref "S1") (pin "3") (pinfunction "3_3") (pintype "passive"))
    )
  )
)
